# 555_project_breadboard_bp-a2_revA.net
KiCad netlist of a schematic drawn in EAGLE
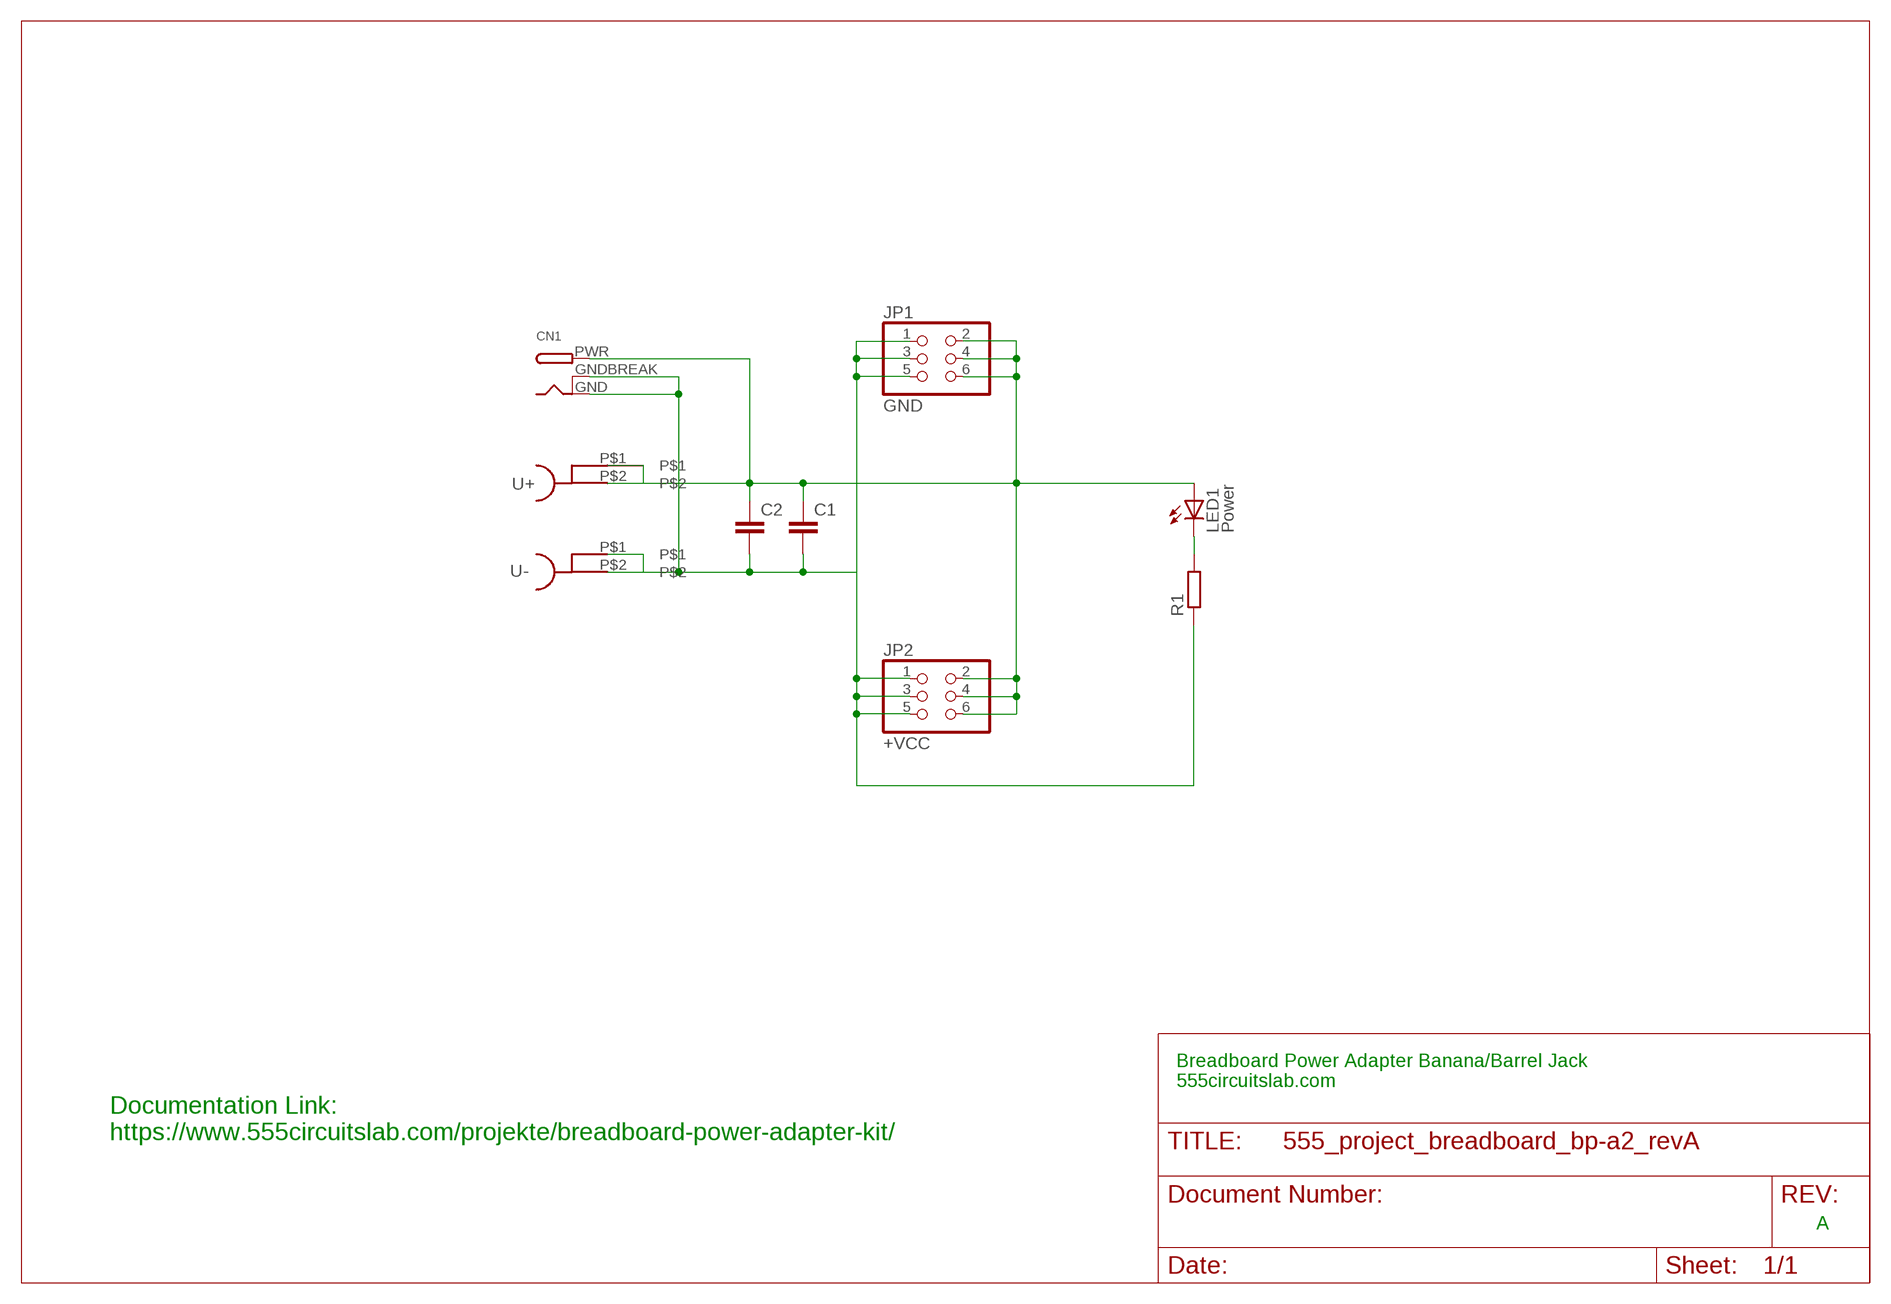
[diagram p0: schematic, sheet 1]

(export (version "E")
  (design (tool "Eeschema 10.0.6"))
  (components
    (comp (ref "C1")
      (value "C-EU025-024X044")
      (footprint "eagle-import:C025-024X044")
      (libsource (lib "eagle-import") (part "C-EU025-024X044"))
    )
    (comp (ref "C2")
      (value "C-EU025-024X044")
      (footprint "eagle-import:C025-024X044")
      (libsource (lib "eagle-import") (part "C-EU025-024X044"))
    )
    (comp (ref "CN1")
      (value "DCBARRELPTH")
      (footprint "eagle-import:DCJACK_2MM_PTH")
      (libsource (lib "eagle-import") (part "DCBARRELPTH"))
    )
    (comp (ref "JP1")
      (value "GND")
      (footprint "eagle-import:2X03")
      (libsource (lib "eagle-import") (part "PINHD-2X3"))
    )
    (comp (ref "JP2")
      (value "+VCC")
      (footprint "eagle-import:2X03")
      (libsource (lib "eagle-import") (part "PINHD-2X3"))
    )
    (comp (ref "LED1")
      (value "Power")
      (footprint "eagle-import:LED5MM")
      (libsource (lib "eagle-import") (part "LED5MM"))
    )
    (comp (ref "R1")
      (value "R-EU_0204/7")
      (footprint "eagle-import:0204_7")
      (libsource (lib "eagle-import") (part "R-EU_0204/7"))
    )
    (comp (ref "U+")
      (value "PCB-BANANA")
      (footprint "eagle-import:PCB-BANANA")
      (libsource (lib "eagle-import") (part "PCB-BANANA"))
    )
    (comp (ref "U-")
      (value "PCB-BANANA")
      (footprint "eagle-import:PCB-BANANA")
      (libsource (lib "eagle-import") (part "PCB-BANANA"))
    )
  )
  (nets
    (net (code "1") (name "Net-(C1-Pad1)") (class "Default")
      (node (ref "C1") (pin "1") (pinfunction "1_1") (pintype "passive"))
      (node (ref "C2") (pin "1") (pinfunction "1_1") (pintype "passive"))
      (node (ref "CN1") (pin "PWR") (pinfunction "PWR_PWR") (pintype "power_in"))
      (node (ref "JP1") (pin "2") (pinfunction "2_2") (pintype "passive"))
      (node (ref "JP1") (pin "4") (pinfunction "4_4") (pintype "passive"))
      (node (ref "JP1") (pin "6") (pinfunction "6_6") (pintype "passive"))
      (node (ref "JP2") (pin "2") (pinfunction "2_2") (pintype "passive"))
      (node (ref "JP2") (pin "4") (pinfunction "4_4") (pintype "passive"))
      (node (ref "JP2") (pin "6") (pinfunction "6_6") (pintype "passive"))
      (node (ref "LED1") (pin "A") (pinfunction "A_A") (pintype "passive"))
      (node (ref "U+") (pin "P$1") (pinfunction "P$1_P$1") (pintype "bidirectional"))
      (node (ref "U+") (pin "P$2") (pinfunction "P$2_P$2") (pintype "bidirectional"))
    )
    (net (code "2") (name "Net-(C1-Pad2)") (class "Default")
      (node (ref "C1") (pin "2") (pinfunction "2_2") (pintype "passive"))
      (node (ref "C2") (pin "2") (pinfunction "2_2") (pintype "passive"))
      (node (ref "CN1") (pin "GND") (pinfunction "GND_GND") (pintype "power_in"))
      (node (ref "CN1") (pin "GNDBREAK") (pinfunction "GNDBREAK_GNDBREAK") (pintype "power_in"))
      (node (ref "JP1") (pin "1") (pinfunction "1_1") (pintype "passive"))
      (node (ref "JP1") (pin "3") (pinfunction "3_3") (pintype "passive"))
      (node (ref "JP1") (pin "5") (pinfunction "5_5") (pintype "passive"))
      (node (ref "JP2") (pin "1") (pinfunction "1_1") (pintype "passive"))
      (node (ref "JP2") (pin "3") (pinfunction "3_3") (pintype "passive"))
      (node (ref "JP2") (pin "5") (pinfunction "5_5") (pintype "passive"))
      (node (ref "R1") (pin "1") (pinfunction "1_1") (pintype "passive"))
      (node (ref "U-") (pin "P$1") (pinfunction "P$1_P$1") (pintype "bidirectional"))
      (node (ref "U-") (pin "P$2") (pinfunction "P$2_P$2") (pintype "bidirectional"))
    )
    (net (code "3") (name "Net-(LED1-C)") (class "Default")
      (node (ref "LED1") (pin "K") (pinfunction "C_K") (pintype "passive"))
      (node (ref "R1") (pin "2") (pinfunction "2_2") (pintype "passive"))
    )
  )
)
